# PC_Microcontroller_Power.net
KiCad netlist of a schematic drawn in Altium Designer
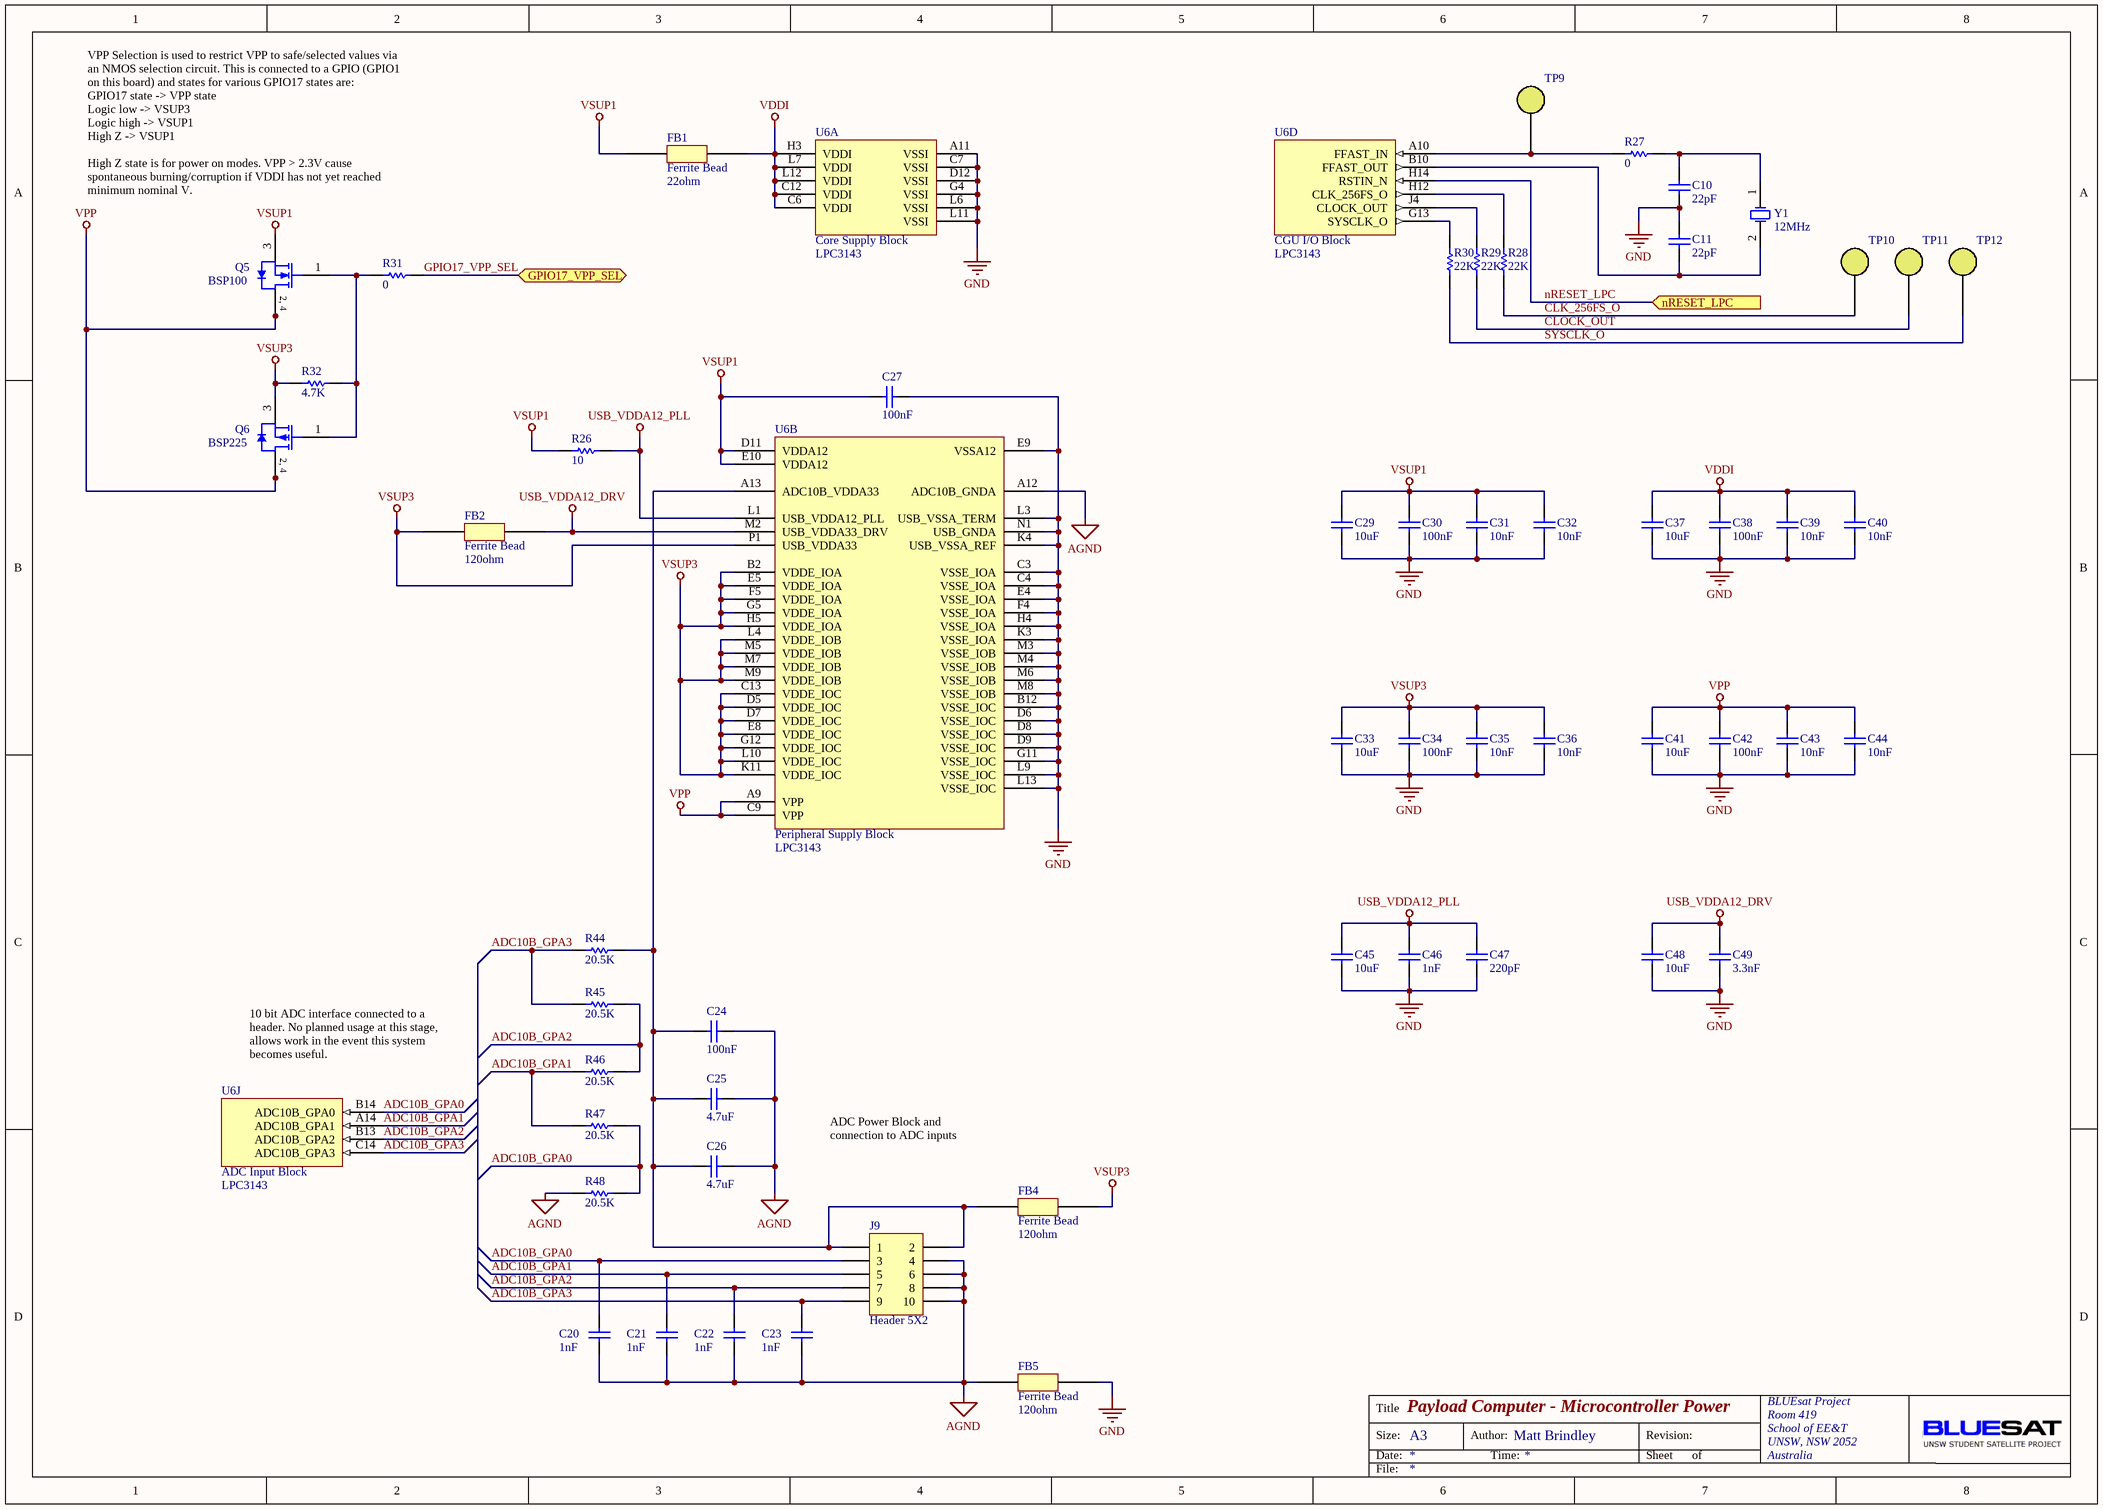
[diagram p0: PC_Microcontroller_Power.SchDoc]

(export (version "E")
  (design (tool "Eeschema 10.0.6"))
  (components
    (comp (ref "C10")
      (value "22pF")
      (footprint "C0805")
      (description "Capacitor (Semiconductor SIM Model)")
      (fields (field (name "Comment") "Cap Semi") (field (name "PUBLISHER") "Altium Limited"))
      (libsource (lib "Miscellaneous Devices") (part "Cap Semi"))
    )
    (comp (ref "C11")
      (value "22pF")
      (footprint "C0805")
      (description "Capacitor (Semiconductor SIM Model)")
      (fields (field (name "Comment") "Cap Semi") (field (name "PUBLISHER") "Altium Limited"))
      (libsource (lib "Miscellaneous Devices") (part "Cap Semi"))
    )
    (comp (ref "C20")
      (value "1nF")
      (footprint "C0805")
      (description "Capacitor (Semiconductor SIM Model)")
      (fields (field (name "Comment") "Cap Semi") (field (name "PUBLISHER") "Altium Limited"))
      (libsource (lib "Miscellaneous Devices") (part "Cap Semi"))
    )
    (comp (ref "C21")
      (value "1nF")
      (footprint "C0805")
      (description "Capacitor (Semiconductor SIM Model)")
      (fields (field (name "Comment") "Cap Semi") (field (name "PUBLISHER") "Altium Limited"))
      (libsource (lib "Miscellaneous Devices") (part "Cap Semi"))
    )
    (comp (ref "C22")
      (value "1nF")
      (footprint "C0805")
      (description "Capacitor (Semiconductor SIM Model)")
      (fields (field (name "Comment") "Cap Semi") (field (name "PUBLISHER") "Altium Limited"))
      (libsource (lib "Miscellaneous Devices") (part "Cap Semi"))
    )
    (comp (ref "C23")
      (value "1nF")
      (footprint "C0805")
      (description "Capacitor (Semiconductor SIM Model)")
      (fields (field (name "Comment") "Cap Semi") (field (name "PUBLISHER") "Altium Limited"))
      (libsource (lib "Miscellaneous Devices") (part "Cap Semi"))
    )
    (comp (ref "C24")
      (value "100nF")
      (footprint "C0805")
      (description "Capacitor (Semiconductor SIM Model)")
      (fields (field (name "Comment") "Cap Semi") (field (name "PUBLISHER") "Altium Limited"))
      (libsource (lib "Miscellaneous Devices") (part "Cap Semi"))
    )
    (comp (ref "C25")
      (value "4.7uF")
      (footprint "C0805")
      (description "Capacitor (Semiconductor SIM Model)")
      (fields (field (name "Comment") "Cap Semi") (field (name "PUBLISHER") "Altium Limited"))
      (libsource (lib "Miscellaneous Devices") (part "Cap Semi"))
    )
    (comp (ref "C26")
      (value "4.7uF")
      (footprint "C0805")
      (description "Capacitor (Semiconductor SIM Model)")
      (fields (field (name "Comment") "Cap Semi") (field (name "PUBLISHER") "Altium Limited"))
      (libsource (lib "Miscellaneous Devices") (part "Cap Semi"))
    )
    (comp (ref "C27")
      (value "100nF")
      (footprint "C0805")
      (description "Capacitor (Semiconductor SIM Model)")
      (fields (field (name "Comment") "Cap Semi") (field (name "PUBLISHER") "Altium Limited"))
      (libsource (lib "Miscellaneous Devices") (part "Cap Semi"))
    )
    (comp (ref "C29")
      (value "10uF")
      (footprint "C0805")
      (description "Capacitor (Semiconductor SIM Model)")
      (fields (field (name "Comment") "Cap Semi") (field (name "PUBLISHER") "Altium Limited"))
      (libsource (lib "Miscellaneous Devices") (part "Cap Semi"))
    )
    (comp (ref "C30")
      (value "100nF")
      (footprint "C0805")
      (description "Capacitor (Semiconductor SIM Model)")
      (fields (field (name "Comment") "Cap Semi") (field (name "PUBLISHER") "Altium Limited"))
      (libsource (lib "Miscellaneous Devices") (part "Cap Semi"))
    )
    (comp (ref "C31")
      (value "10nF")
      (footprint "C0805")
      (description "Capacitor (Semiconductor SIM Model)")
      (fields (field (name "Comment") "Cap Semi") (field (name "PUBLISHER") "Altium Limited"))
      (libsource (lib "Miscellaneous Devices") (part "Cap Semi"))
    )
    (comp (ref "C32")
      (value "10nF")
      (footprint "C0805")
      (description "Capacitor (Semiconductor SIM Model)")
      (fields (field (name "Comment") "Cap Semi") (field (name "PUBLISHER") "Altium Limited"))
      (libsource (lib "Miscellaneous Devices") (part "Cap Semi"))
    )
    (comp (ref "C33")
      (value "10uF")
      (footprint "C0805")
      (description "Capacitor (Semiconductor SIM Model)")
      (fields (field (name "Comment") "Cap Semi") (field (name "PUBLISHER") "Altium Limited"))
      (libsource (lib "Miscellaneous Devices") (part "Cap Semi"))
    )
    (comp (ref "C34")
      (value "100nF")
      (footprint "C0805")
      (description "Capacitor (Semiconductor SIM Model)")
      (fields (field (name "Comment") "Cap Semi") (field (name "PUBLISHER") "Altium Limited"))
      (libsource (lib "Miscellaneous Devices") (part "Cap Semi"))
    )
    (comp (ref "C35")
      (value "10nF")
      (footprint "C0805")
      (description "Capacitor (Semiconductor SIM Model)")
      (fields (field (name "Comment") "Cap Semi") (field (name "PUBLISHER") "Altium Limited"))
      (libsource (lib "Miscellaneous Devices") (part "Cap Semi"))
    )
    (comp (ref "C36")
      (value "10nF")
      (footprint "C0805")
      (description "Capacitor (Semiconductor SIM Model)")
      (fields (field (name "Comment") "Cap Semi") (field (name "PUBLISHER") "Altium Limited"))
      (libsource (lib "Miscellaneous Devices") (part "Cap Semi"))
    )
    (comp (ref "C37")
      (value "10uF")
      (footprint "C0805")
      (description "Capacitor (Semiconductor SIM Model)")
      (fields (field (name "Comment") "Cap Semi") (field (name "PUBLISHER") "Altium Limited"))
      (libsource (lib "Miscellaneous Devices") (part "Cap Semi"))
    )
    (comp (ref "C38")
      (value "100nF")
      (footprint "C0805")
      (description "Capacitor (Semiconductor SIM Model)")
      (fields (field (name "Comment") "Cap Semi") (field (name "PUBLISHER") "Altium Limited"))
      (libsource (lib "Miscellaneous Devices") (part "Cap Semi"))
    )
    (comp (ref "C39")
      (value "10nF")
      (footprint "C0805")
      (description "Capacitor (Semiconductor SIM Model)")
      (fields (field (name "Comment") "Cap Semi") (field (name "PUBLISHER") "Altium Limited"))
      (libsource (lib "Miscellaneous Devices") (part "Cap Semi"))
    )
    (comp (ref "C40")
      (value "10nF")
      (footprint "C0805")
      (description "Capacitor (Semiconductor SIM Model)")
      (fields (field (name "Comment") "Cap Semi") (field (name "PUBLISHER") "Altium Limited"))
      (libsource (lib "Miscellaneous Devices") (part "Cap Semi"))
    )
    (comp (ref "C41")
      (value "10uF")
      (footprint "C0805")
      (description "Capacitor (Semiconductor SIM Model)")
      (fields (field (name "Comment") "Cap Semi") (field (name "PUBLISHER") "Altium Limited"))
      (libsource (lib "Miscellaneous Devices") (part "Cap Semi"))
    )
    (comp (ref "C42")
      (value "100nF")
      (footprint "C0805")
      (description "Capacitor (Semiconductor SIM Model)")
      (fields (field (name "Comment") "Cap Semi") (field (name "PUBLISHER") "Altium Limited"))
      (libsource (lib "Miscellaneous Devices") (part "Cap Semi"))
    )
    (comp (ref "C43")
      (value "10nF")
      (footprint "C0805")
      (description "Capacitor (Semiconductor SIM Model)")
      (fields (field (name "Comment") "Cap Semi") (field (name "PUBLISHER") "Altium Limited"))
      (libsource (lib "Miscellaneous Devices") (part "Cap Semi"))
    )
    (comp (ref "C44")
      (value "10nF")
      (footprint "C0805")
      (description "Capacitor (Semiconductor SIM Model)")
      (fields (field (name "Comment") "Cap Semi") (field (name "PUBLISHER") "Altium Limited"))
      (libsource (lib "Miscellaneous Devices") (part "Cap Semi"))
    )
    (comp (ref "C45")
      (value "10uF")
      (footprint "C0805")
      (description "Capacitor (Semiconductor SIM Model)")
      (fields (field (name "Comment") "Cap Semi") (field (name "PUBLISHER") "Altium Limited"))
      (libsource (lib "Miscellaneous Devices") (part "Cap Semi"))
    )
    (comp (ref "C46")
      (value "1nF")
      (footprint "C0805")
      (description "Capacitor (Semiconductor SIM Model)")
      (fields (field (name "Comment") "Cap Semi") (field (name "PUBLISHER") "Altium Limited"))
      (libsource (lib "Miscellaneous Devices") (part "Cap Semi"))
    )
    (comp (ref "C47")
      (value "220pF")
      (footprint "C0805")
      (description "Capacitor (Semiconductor SIM Model)")
      (fields (field (name "Comment") "Cap Semi") (field (name "PUBLISHER") "Altium Limited"))
      (libsource (lib "Miscellaneous Devices") (part "Cap Semi"))
    )
    (comp (ref "C48")
      (value "10uF")
      (footprint "C0805")
      (description "Capacitor (Semiconductor SIM Model)")
      (fields (field (name "Comment") "Cap Semi") (field (name "PUBLISHER") "Altium Limited"))
      (libsource (lib "Miscellaneous Devices") (part "Cap Semi"))
    )
    (comp (ref "C49")
      (value "3.3nF")
      (footprint "C0805")
      (description "Capacitor (Semiconductor SIM Model)")
      (fields (field (name "Comment") "Cap Semi") (field (name "PUBLISHER") "Altium Limited"))
      (libsource (lib "Miscellaneous Devices") (part "Cap Semi"))
    )
    (comp (ref "FB1")
      (value "Ferrite Bead")
      (footprint "AXIAL-0.3")
      (description "Standard Ferrite Bead")
      (fields (field (name "ALTIUM_VALUE") "22ohm") (field (name "PUBLISHER") "Altium Limited"))
      (libsource (lib "PC_Components") (part "Ferrite Bead"))
    )
    (comp (ref "FB2")
      (value "Ferrite Bead")
      (footprint "AXIAL-0.3")
      (description "Standard Ferrite Bead")
      (fields (field (name "ALTIUM_VALUE") "120ohm") (field (name "PUBLISHER") "Altium Limited"))
      (libsource (lib "PC_Components") (part "Ferrite Bead"))
    )
    (comp (ref "FB4")
      (value "Ferrite Bead")
      (footprint "AXIAL-0.3")
      (description "Standard Ferrite Bead")
      (fields (field (name "ALTIUM_VALUE") "120ohm") (field (name "PUBLISHER") "Altium Limited"))
      (libsource (lib "PC_Components") (part "Ferrite Bead"))
    )
    (comp (ref "FB5")
      (value "Ferrite Bead")
      (footprint "AXIAL-0.3")
      (description "Standard Ferrite Bead")
      (fields (field (name "ALTIUM_VALUE") "120ohm") (field (name "PUBLISHER") "Altium Limited"))
      (libsource (lib "PC_Components") (part "Ferrite Bead"))
    )
    (comp (ref "J9")
      (value "Header 5X2")
      (footprint "HDR2X5")
      (description "Header, 5-Pin, Dual row")
      (fields (field (name "PUBLISHER") "Altium Limited"))
      (libsource (lib "Miscellaneous Connectors") (part "Header 5X2"))
    )
    (comp (ref "Q5")
      (value "BSP100")
      (footprint "SOT223_N")
      (description "N-channel Enhancement Mode MOSFET")
      (fields (field (name "PUBLISHER") "Altium Limited"))
      (libsource (lib "Philips Discrete MOSFET - Power") (part "BSP100"))
    )
    (comp (ref "Q6")
      (value "BSP225")
      (footprint "SOT223_N")
      (description "P-channel Enhancement Mode Vertical D-MOSFET")
      (fields (field (name "PUBLISHER") "Altium Limited"))
      (libsource (lib "Philips Discrete MOSFET - Power") (part "BSP225"))
    )
    (comp (ref "R26")
      (value "10")
      (footprint "6-0805_L")
      (description "Semiconductor Resistor")
      (fields (field (name "Comment") "Res Semi") (field (name "PUBLISHER") "Altium Limited"))
      (libsource (lib "Miscellaneous Devices") (part "Res Semi"))
    )
    (comp (ref "R27")
      (value "0")
      (footprint "6-0805_L")
      (description "Semiconductor Resistor")
      (fields (field (name "Comment") "Res Semi") (field (name "PUBLISHER") "Altium Limited"))
      (libsource (lib "Miscellaneous Devices") (part "Res Semi"))
    )
    (comp (ref "R28")
      (value "22K")
      (footprint "6-0805_L")
      (description "Semiconductor Resistor")
      (fields (field (name "Comment") "Res Semi") (field (name "PUBLISHER") "Altium Limited"))
      (libsource (lib "Miscellaneous Devices") (part "Res Semi"))
    )
    (comp (ref "R29")
      (value "22K")
      (footprint "6-0805_L")
      (description "Semiconductor Resistor")
      (fields (field (name "Comment") "Res Semi") (field (name "PUBLISHER") "Altium Limited"))
      (libsource (lib "Miscellaneous Devices") (part "Res Semi"))
    )
    (comp (ref "R30")
      (value "22K")
      (footprint "6-0805_L")
      (description "Semiconductor Resistor")
      (fields (field (name "Comment") "Res Semi") (field (name "PUBLISHER") "Altium Limited"))
      (libsource (lib "Miscellaneous Devices") (part "Res Semi"))
    )
    (comp (ref "R31")
      (value "0")
      (footprint "6-0805_L")
      (description "Semiconductor Resistor")
      (fields (field (name "Comment") "Res Semi") (field (name "PUBLISHER") "Altium Limited"))
      (libsource (lib "Miscellaneous Devices") (part "Res Semi"))
    )
    (comp (ref "R32")
      (value "4.7K")
      (footprint "6-0805_L")
      (description "Semiconductor Resistor")
      (fields (field (name "Comment") "Res Semi") (field (name "PUBLISHER") "Altium Limited"))
      (libsource (lib "Miscellaneous Devices") (part "Res Semi"))
    )
    (comp (ref "R44")
      (value "20.5K")
      (footprint "6-0805_L")
      (description "Semiconductor Resistor")
      (fields (field (name "Comment") "Res Semi") (field (name "PUBLISHER") "Altium Limited"))
      (libsource (lib "Miscellaneous Devices") (part "Res Semi"))
    )
    (comp (ref "R45")
      (value "20.5K")
      (footprint "6-0805_L")
      (description "Semiconductor Resistor")
      (fields (field (name "Comment") "Res Semi") (field (name "PUBLISHER") "Altium Limited"))
      (libsource (lib "Miscellaneous Devices") (part "Res Semi"))
    )
    (comp (ref "R46")
      (value "20.5K")
      (footprint "6-0805_L")
      (description "Semiconductor Resistor")
      (fields (field (name "Comment") "Res Semi") (field (name "PUBLISHER") "Altium Limited"))
      (libsource (lib "Miscellaneous Devices") (part "Res Semi"))
    )
    (comp (ref "R47")
      (value "20.5K")
      (footprint "6-0805_L")
      (description "Semiconductor Resistor")
      (fields (field (name "Comment") "Res Semi") (field (name "PUBLISHER") "Altium Limited"))
      (libsource (lib "Miscellaneous Devices") (part "Res Semi"))
    )
    (comp (ref "R48")
      (value "20.5K")
      (footprint "6-0805_L")
      (description "Semiconductor Resistor")
      (fields (field (name "Comment") "Res Semi") (field (name "PUBLISHER") "Altium Limited"))
      (libsource (lib "Miscellaneous Devices") (part "Res Semi"))
    )
    (comp (ref "TP9")
      (value "Test Point")
      (footprint "PIN1")
      (description "Test point")
      (fields (field (name "PUBLISHER") "Altium Limited"))
      (libsource (lib "PC_Components") (part "Test Point"))
    )
    (comp (ref "TP10")
      (value "Test Point")
      (footprint "PIN1")
      (description "Test point")
      (fields (field (name "PUBLISHER") "Altium Limited"))
      (libsource (lib "PC_Components") (part "Test Point"))
    )
    (comp (ref "TP11")
      (value "Test Point")
      (footprint "PIN1")
      (description "Test point")
      (fields (field (name "PUBLISHER") "Altium Limited"))
      (libsource (lib "PC_Components") (part "Test Point"))
    )
    (comp (ref "TP12")
      (value "Test Point")
      (footprint "PIN1")
      (description "Test point")
      (fields (field (name "PUBLISHER") "Altium Limited"))
      (libsource (lib "PC_Components") (part "Test Point"))
    )
    (comp (ref "U6")
      (value "LPC3143")
      (footprint "PC_Footprints:BGA180C80P14X14_1200X1200X120")
      (description "NXP ARM9 based microcontroller")
      (fields (field (name "PUBLISHER") "BLUEsat Project"))
      (libsource (lib "PC_Components") (part "LPC3143"))
    )
    (comp (ref "Y1")
      (value "12MHz")
      (footprint "RAD-0.3")
      (description "Crystal Oscillator")
      (fields (field (name "Comment") "XTAL") (field (name "PUBLISHER") "Altium Limited"))
      (libsource (lib "Miscellaneous Devices") (part "XTAL"))
    )
  )
  (nets
    (net (code "1") (name "/ADC10B_GPA0") (class "Default")
      (node (ref "C20") (pin "2") (pinfunction "2_2") (pintype "passive"))
      (node (ref "J9") (pin "3") (pinfunction "3_3") (pintype "passive"))
      (node (ref "R47") (pin "2") (pinfunction "2_2") (pintype "passive"))
      (node (ref "R48") (pin "2") (pinfunction "2_2") (pintype "passive"))
      (node (ref "U6") (pin "B14") (pinfunction "ADC10B_GPA0_B14") (pintype "input"))
    )
    (net (code "2") (name "/ADC10B_GPA1") (class "Default")
      (node (ref "C21") (pin "2") (pinfunction "2_2") (pintype "passive"))
      (node (ref "J9") (pin "5") (pinfunction "5_5") (pintype "passive"))
      (node (ref "R46") (pin "1") (pinfunction "1_1") (pintype "passive"))
      (node (ref "R47") (pin "1") (pinfunction "1_1") (pintype "passive"))
      (node (ref "U6") (pin "A14") (pinfunction "ADC10B_GPA1_A14") (pintype "input"))
    )
    (net (code "3") (name "/ADC10B_GPA2") (class "Default")
      (node (ref "C22") (pin "2") (pinfunction "2_2") (pintype "passive"))
      (node (ref "J9") (pin "7") (pinfunction "7_7") (pintype "passive"))
      (node (ref "R45") (pin "2") (pinfunction "2_2") (pintype "passive"))
      (node (ref "R46") (pin "2") (pinfunction "2_2") (pintype "passive"))
      (node (ref "U6") (pin "B13") (pinfunction "ADC10B_GPA2_B13") (pintype "input"))
    )
    (net (code "4") (name "/ADC10B_GPA3") (class "Default")
      (node (ref "C23") (pin "2") (pinfunction "2_2") (pintype "passive"))
      (node (ref "J9") (pin "9") (pinfunction "9_9") (pintype "passive"))
      (node (ref "R44") (pin "1") (pinfunction "1_1") (pintype "passive"))
      (node (ref "R45") (pin "1") (pinfunction "1_1") (pintype "passive"))
      (node (ref "U6") (pin "C14") (pinfunction "ADC10B_GPA3_C14") (pintype "input"))
    )
    (net (code "5") (name "/CLK_256FS_O") (class "Default")
      (node (ref "R28") (pin "1") (pinfunction "1_1") (pintype "passive"))
      (node (ref "TP10") (pin "1") (pinfunction "1_1") (pintype "passive"))
    )
    (net (code "6") (name "/CLOCK_OUT") (class "Default")
      (node (ref "R29") (pin "1") (pinfunction "1_1") (pintype "passive"))
      (node (ref "TP11") (pin "1") (pinfunction "1_1") (pintype "passive"))
    )
    (net (code "7") (name "/GPIO17_VPP_SEL") (class "Default")
      (node (ref "R31") (pin "2") (pinfunction "2_2") (pintype "passive"))
    )
    (net (code "8") (name "/SYSCLK_O") (class "Default")
      (node (ref "R30") (pin "1") (pinfunction "1_1") (pintype "passive"))
      (node (ref "TP12") (pin "1") (pinfunction "1_1") (pintype "passive"))
    )
    (net (code "9") (name "/nRESET_LPC") (class "Default")
      (node (ref "U6") (pin "H14") (pinfunction "RSTIN_N_H14") (pintype "input"))
    )
    (net (code "10") (name "AGND") (class "Default")
      (node (ref "C20") (pin "1") (pinfunction "1_1") (pintype "passive"))
      (node (ref "C21") (pin "1") (pinfunction "1_1") (pintype "passive"))
      (node (ref "C22") (pin "1") (pinfunction "1_1") (pintype "passive"))
      (node (ref "C23") (pin "1") (pinfunction "1_1") (pintype "passive"))
      (node (ref "C24") (pin "1") (pinfunction "1_1") (pintype "passive"))
      (node (ref "C25") (pin "1") (pinfunction "1_1") (pintype "passive"))
      (node (ref "C26") (pin "1") (pinfunction "1_1") (pintype "passive"))
      (node (ref "FB5") (pin "2") (pinfunction "2_2") (pintype "passive"))
      (node (ref "J9") (pin "10") (pinfunction "10_10") (pintype "passive"))
      (node (ref "J9") (pin "4") (pinfunction "4_4") (pintype "passive"))
      (node (ref "J9") (pin "6") (pinfunction "6_6") (pintype "passive"))
      (node (ref "J9") (pin "8") (pinfunction "8_8") (pintype "passive"))
      (node (ref "R48") (pin "1") (pinfunction "1_1") (pintype "passive"))
      (node (ref "U6") (pin "A12") (pinfunction "ADC10B_GNDA_A12") (pintype "power_in"))
    )
    (net (code "11") (name "GND") (class "Default")
      (node (ref "C10") (pin "2") (pinfunction "2_2") (pintype "passive"))
      (node (ref "C11") (pin "1") (pinfunction "1_1") (pintype "passive"))
      (node (ref "C27") (pin "1") (pinfunction "1_1") (pintype "passive"))
      (node (ref "C29") (pin "2") (pinfunction "2_2") (pintype "passive"))
      (node (ref "C30") (pin "2") (pinfunction "2_2") (pintype "passive"))
      (node (ref "C31") (pin "2") (pinfunction "2_2") (pintype "passive"))
      (node (ref "C32") (pin "2") (pinfunction "2_2") (pintype "passive"))
      (node (ref "C33") (pin "2") (pinfunction "2_2") (pintype "passive"))
      (node (ref "C34") (pin "2") (pinfunction "2_2") (pintype "passive"))
      (node (ref "C35") (pin "2") (pinfunction "2_2") (pintype "passive"))
      (node (ref "C36") (pin "2") (pinfunction "2_2") (pintype "passive"))
      (node (ref "C37") (pin "2") (pinfunction "2_2") (pintype "passive"))
      (node (ref "C38") (pin "2") (pinfunction "2_2") (pintype "passive"))
      (node (ref "C39") (pin "2") (pinfunction "2_2") (pintype "passive"))
      (node (ref "C40") (pin "2") (pinfunction "2_2") (pintype "passive"))
      (node (ref "C41") (pin "2") (pinfunction "2_2") (pintype "passive"))
      (node (ref "C42") (pin "2") (pinfunction "2_2") (pintype "passive"))
      (node (ref "C43") (pin "2") (pinfunction "2_2") (pintype "passive"))
      (node (ref "C44") (pin "2") (pinfunction "2_2") (pintype "passive"))
      (node (ref "C45") (pin "2") (pinfunction "2_2") (pintype "passive"))
      (node (ref "C46") (pin "2") (pinfunction "2_2") (pintype "passive"))
      (node (ref "C47") (pin "2") (pinfunction "2_2") (pintype "passive"))
      (node (ref "C48") (pin "2") (pinfunction "2_2") (pintype "passive"))
      (node (ref "C49") (pin "2") (pinfunction "2_2") (pintype "passive"))
      (node (ref "FB5") (pin "1") (pinfunction "1_1") (pintype "passive"))
      (node (ref "U6") (pin "A11") (pinfunction "VSSI_A11") (pintype "power_in"))
      (node (ref "U6") (pin "B12") (pinfunction "VSSE_IOC_B12") (pintype "power_in"))
      (node (ref "U6") (pin "C3") (pinfunction "VSSE_IOA_C3") (pintype "power_in"))
      (node (ref "U6") (pin "C4") (pinfunction "VSSE_IOA_C4") (pintype "power_in"))
      (node (ref "U6") (pin "C7") (pinfunction "VSSI_C7") (pintype "power_in"))
      (node (ref "U6") (pin "D12") (pinfunction "VSSI_D12") (pintype "power_in"))
      (node (ref "U6") (pin "D6") (pinfunction "VSSE_IOC_D6") (pintype "power_in"))
      (node (ref "U6") (pin "D8") (pinfunction "VSSE_IOC_D8") (pintype "power_in"))
      (node (ref "U6") (pin "D9") (pinfunction "VSSE_IOC_D9") (pintype "power_in"))
      (node (ref "U6") (pin "E4") (pinfunction "VSSE_IOA_E4") (pintype "power_in"))
      (node (ref "U6") (pin "E9") (pinfunction "VSSA12_E9") (pintype "power_in"))
      (node (ref "U6") (pin "F4") (pinfunction "VSSE_IOA_F4") (pintype "power_in"))
      (node (ref "U6") (pin "G11") (pinfunction "VSSE_IOC_G11") (pintype "power_in"))
      (node (ref "U6") (pin "G4") (pinfunction "VSSI_G4") (pintype "power_in"))
      (node (ref "U6") (pin "H4") (pinfunction "VSSE_IOA_H4") (pintype "power_in"))
      (node (ref "U6") (pin "K3") (pinfunction "VSSE_IOA_K3") (pintype "power_in"))
      (node (ref "U6") (pin "K4") (pinfunction "USB_VSSA_REF_K4") (pintype "power_in"))
      (node (ref "U6") (pin "L11") (pinfunction "VSSI_L11") (pintype "power_in"))
      (node (ref "U6") (pin "L13") (pinfunction "VSSE_IOC_L13") (pintype "power_in"))
      (node (ref "U6") (pin "L3") (pinfunction "USB_VSSA_TERM_L3") (pintype "power_in"))
      (node (ref "U6") (pin "L6") (pinfunction "VSSI_L6") (pintype "power_in"))
      (node (ref "U6") (pin "L9") (pinfunction "VSSE_IOC_L9") (pintype "power_in"))
      (node (ref "U6") (pin "M3") (pinfunction "VSSE_IOB_M3") (pintype "power_in"))
      (node (ref "U6") (pin "M4") (pinfunction "VSSE_IOB_M4") (pintype "power_in"))
      (node (ref "U6") (pin "M6") (pinfunction "VSSE_IOB_M6") (pintype "power_in"))
      (node (ref "U6") (pin "M8") (pinfunction "VSSE_IOB_M8") (pintype "power_in"))
      (node (ref "U6") (pin "N1") (pinfunction "USB_GNDA_N1") (pintype "power_in"))
    )
    (net (code "12") (name "Net-(Q5-G)") (class "Default")
      (node (ref "Q5") (pin "1") (pinfunction "G_1") (pintype "passive"))
      (node (ref "Q6") (pin "1") (pinfunction "G_1") (pintype "passive"))
      (node (ref "R31") (pin "1") (pinfunction "1_1") (pintype "passive"))
      (node (ref "R32") (pin "2") (pinfunction "2_2") (pintype "passive"))
    )
    (net (code "13") (name "Net-(U6B-ADC10B_VDDA33)") (class "Default")
      (node (ref "C24") (pin "2") (pinfunction "2_2") (pintype "passive"))
      (node (ref "C25") (pin "2") (pinfunction "2_2") (pintype "passive"))
      (node (ref "C26") (pin "2") (pinfunction "2_2") (pintype "passive"))
      (node (ref "FB4") (pin "2") (pinfunction "2_2") (pintype "passive"))
      (node (ref "J9") (pin "1") (pinfunction "1_1") (pintype "passive"))
      (node (ref "J9") (pin "2") (pinfunction "2_2") (pintype "passive"))
      (node (ref "R44") (pin "2") (pinfunction "2_2") (pintype "passive"))
      (node (ref "U6") (pin "A13") (pinfunction "ADC10B_VDDA33_A13") (pintype "power_in"))
    )
    (net (code "14") (name "Net-(U6D-CLK_256FS_O)") (class "Default")
      (node (ref "R28") (pin "2") (pinfunction "2_2") (pintype "passive"))
      (node (ref "U6") (pin "H12") (pinfunction "CLK_256FS_O_H12") (pintype "output"))
    )
    (net (code "15") (name "Net-(U6D-CLOCK_OUT)") (class "Default")
      (node (ref "R29") (pin "2") (pinfunction "2_2") (pintype "passive"))
      (node (ref "U6") (pin "J4") (pinfunction "CLOCK_OUT_J4") (pintype "output"))
    )
    (net (code "16") (name "Net-(U6D-FFAST_IN)") (class "Default")
      (node (ref "R27") (pin "1") (pinfunction "1_1") (pintype "passive"))
      (node (ref "TP9") (pin "1") (pinfunction "1_1") (pintype "passive"))
      (node (ref "U6") (pin "A10") (pinfunction "FFAST_IN_A10") (pintype "input"))
    )
    (net (code "17") (name "Net-(U6D-FFAST_OUT)") (class "Default")
      (node (ref "C11") (pin "2") (pinfunction "2_2") (pintype "passive"))
      (node (ref "U6") (pin "B10") (pinfunction "FFAST_OUT_B10") (pintype "output"))
      (node (ref "Y1") (pin "2") (pinfunction "OSC2_2") (pintype "passive"))
    )
    (net (code "18") (name "Net-(U6D-SYSCLK_O)") (class "Default")
      (node (ref "R30") (pin "2") (pinfunction "2_2") (pintype "passive"))
      (node (ref "U6") (pin "G13") (pinfunction "SYSCLK_O_G13") (pintype "output"))
    )
    (net (code "19") (name "Net-(Y1-OSC1)") (class "Default")
      (node (ref "C10") (pin "1") (pinfunction "1_1") (pintype "passive"))
      (node (ref "R27") (pin "2") (pinfunction "2_2") (pintype "passive"))
      (node (ref "Y1") (pin "1") (pinfunction "OSC1_1") (pintype "passive"))
    )
    (net (code "20") (name "USB_VDDA12_DRV") (class "Default")
      (node (ref "C48") (pin "1") (pinfunction "1_1") (pintype "passive"))
      (node (ref "C49") (pin "1") (pinfunction "1_1") (pintype "passive"))
      (node (ref "FB2") (pin "1") (pinfunction "1_1") (pintype "passive"))
      (node (ref "U6") (pin "M2") (pinfunction "USB_VDDA33_DRV_M2") (pintype "power_in"))
    )
    (net (code "21") (name "USB_VDDA12_PLL") (class "Default")
      (node (ref "C45") (pin "1") (pinfunction "1_1") (pintype "passive"))
      (node (ref "C46") (pin "1") (pinfunction "1_1") (pintype "passive"))
      (node (ref "C47") (pin "1") (pinfunction "1_1") (pintype "passive"))
      (node (ref "R26") (pin "2") (pinfunction "2_2") (pintype "passive"))
      (node (ref "U6") (pin "L1") (pinfunction "USB_VDDA12_PLL_L1") (pintype "power_in"))
    )
    (net (code "22") (name "VDDI") (class "Default")
      (node (ref "C37") (pin "1") (pinfunction "1_1") (pintype "passive"))
      (node (ref "C38") (pin "1") (pinfunction "1_1") (pintype "passive"))
      (node (ref "C39") (pin "1") (pinfunction "1_1") (pintype "passive"))
      (node (ref "C40") (pin "1") (pinfunction "1_1") (pintype "passive"))
      (node (ref "FB1") (pin "1") (pinfunction "1_1") (pintype "passive"))
      (node (ref "U6") (pin "C12") (pinfunction "VDDI_C12") (pintype "power_in"))
      (node (ref "U6") (pin "C6") (pinfunction "VDDI_C6") (pintype "power_in"))
      (node (ref "U6") (pin "H3") (pinfunction "VDDI_H3") (pintype "power_in"))
      (node (ref "U6") (pin "L12") (pinfunction "VDDI_L12") (pintype "power_in"))
      (node (ref "U6") (pin "L7") (pinfunction "VDDI_L7") (pintype "power_in"))
    )
    (net (code "23") (name "VPP") (class "Default")
      (node (ref "C41") (pin "1") (pinfunction "1_1") (pintype "passive"))
      (node (ref "C42") (pin "1") (pinfunction "1_1") (pintype "passive"))
      (node (ref "C43") (pin "1") (pinfunction "1_1") (pintype "passive"))
      (node (ref "C44") (pin "1") (pinfunction "1_1") (pintype "passive"))
      (node (ref "Q5") (pin "2") (pinfunction "D_2") (pintype "passive"))
      (node (ref "Q5") (pin "4") (pinfunction "D_4") (pintype "passive"))
      (node (ref "Q6") (pin "2") (pinfunction "D_2") (pintype "passive"))
      (node (ref "Q6") (pin "4") (pinfunction "D_4") (pintype "passive"))
      (node (ref "U6") (pin "A9") (pinfunction "VPP_A9") (pintype "power_in"))
      (node (ref "U6") (pin "C9") (pinfunction "VPP_C9") (pintype "power_in"))
    )
    (net (code "24") (name "VSUP1") (class "Default")
      (node (ref "C27") (pin "2") (pinfunction "2_2") (pintype "passive"))
      (node (ref "C29") (pin "1") (pinfunction "1_1") (pintype "passive"))
      (node (ref "C30") (pin "1") (pinfunction "1_1") (pintype "passive"))
      (node (ref "C31") (pin "1") (pinfunction "1_1") (pintype "passive"))
      (node (ref "C32") (pin "1") (pinfunction "1_1") (pintype "passive"))
      (node (ref "FB1") (pin "2") (pinfunction "2_2") (pintype "passive"))
      (node (ref "Q5") (pin "3") (pinfunction "S_3") (pintype "passive"))
      (node (ref "R26") (pin "1") (pinfunction "1_1") (pintype "passive"))
      (node (ref "U6") (pin "D11") (pinfunction "VDDA12_D11") (pintype "power_in"))
      (node (ref "U6") (pin "E10") (pinfunction "VDDA12_E10") (pintype "power_in"))
    )
    (net (code "25") (name "VSUP3") (class "Default")
      (node (ref "C33") (pin "1") (pinfunction "1_1") (pintype "passive"))
      (node (ref "C34") (pin "1") (pinfunction "1_1") (pintype "passive"))
      (node (ref "C35") (pin "1") (pinfunction "1_1") (pintype "passive"))
      (node (ref "C36") (pin "1") (pinfunction "1_1") (pintype "passive"))
      (node (ref "FB2") (pin "2") (pinfunction "2_2") (pintype "passive"))
      (node (ref "FB4") (pin "1") (pinfunction "1_1") (pintype "passive"))
      (node (ref "Q6") (pin "3") (pinfunction "S_3") (pintype "passive"))
      (node (ref "R32") (pin "1") (pinfunction "1_1") (pintype "passive"))
      (node (ref "U6") (pin "B2") (pinfunction "VDDE_IOA_B2") (pintype "power_in"))
      (node (ref "U6") (pin "C13") (pinfunction "VDDE_IOC_C13") (pintype "power_in"))
      (node (ref "U6") (pin "D5") (pinfunction "VDDE_IOC_D5") (pintype "power_in"))
      (node (ref "U6") (pin "D7") (pinfunction "VDDE_IOC_D7") (pintype "power_in"))
      (node (ref "U6") (pin "E5") (pinfunction "VDDE_IOA_E5") (pintype "power_in"))
      (node (ref "U6") (pin "E8") (pinfunction "VDDE_IOC_E8") (pintype "power_in"))
      (node (ref "U6") (pin "F5") (pinfunction "VDDE_IOA_F5") (pintype "power_in"))
      (node (ref "U6") (pin "G12") (pinfunction "VDDE_IOC_G12") (pintype "power_in"))
      (node (ref "U6") (pin "G5") (pinfunction "VDDE_IOA_G5") (pintype "power_in"))
      (node (ref "U6") (pin "H5") (pinfunction "VDDE_IOA_H5") (pintype "power_in"))
      (node (ref "U6") (pin "K11") (pinfunction "VDDE_IOC_K11") (pintype "power_in"))
      (node (ref "U6") (pin "L10") (pinfunction "VDDE_IOC_L10") (pintype "power_in"))
      (node (ref "U6") (pin "L4") (pinfunction "VDDE_IOB_L4") (pintype "power_in"))
      (node (ref "U6") (pin "M5") (pinfunction "VDDE_IOB_M5") (pintype "power_in"))
      (node (ref "U6") (pin "M7") (pinfunction "VDDE_IOB_M7") (pintype "power_in"))
      (node (ref "U6") (pin "M9") (pinfunction "VDDE_IOB_M9") (pintype "power_in"))
      (node (ref "U6") (pin "P1") (pinfunction "USB_VDDA33_P1") (pintype "power_in"))
    )
  )
)
